# power.net
KiCad netlist of a schematic drawn in Altium Designer
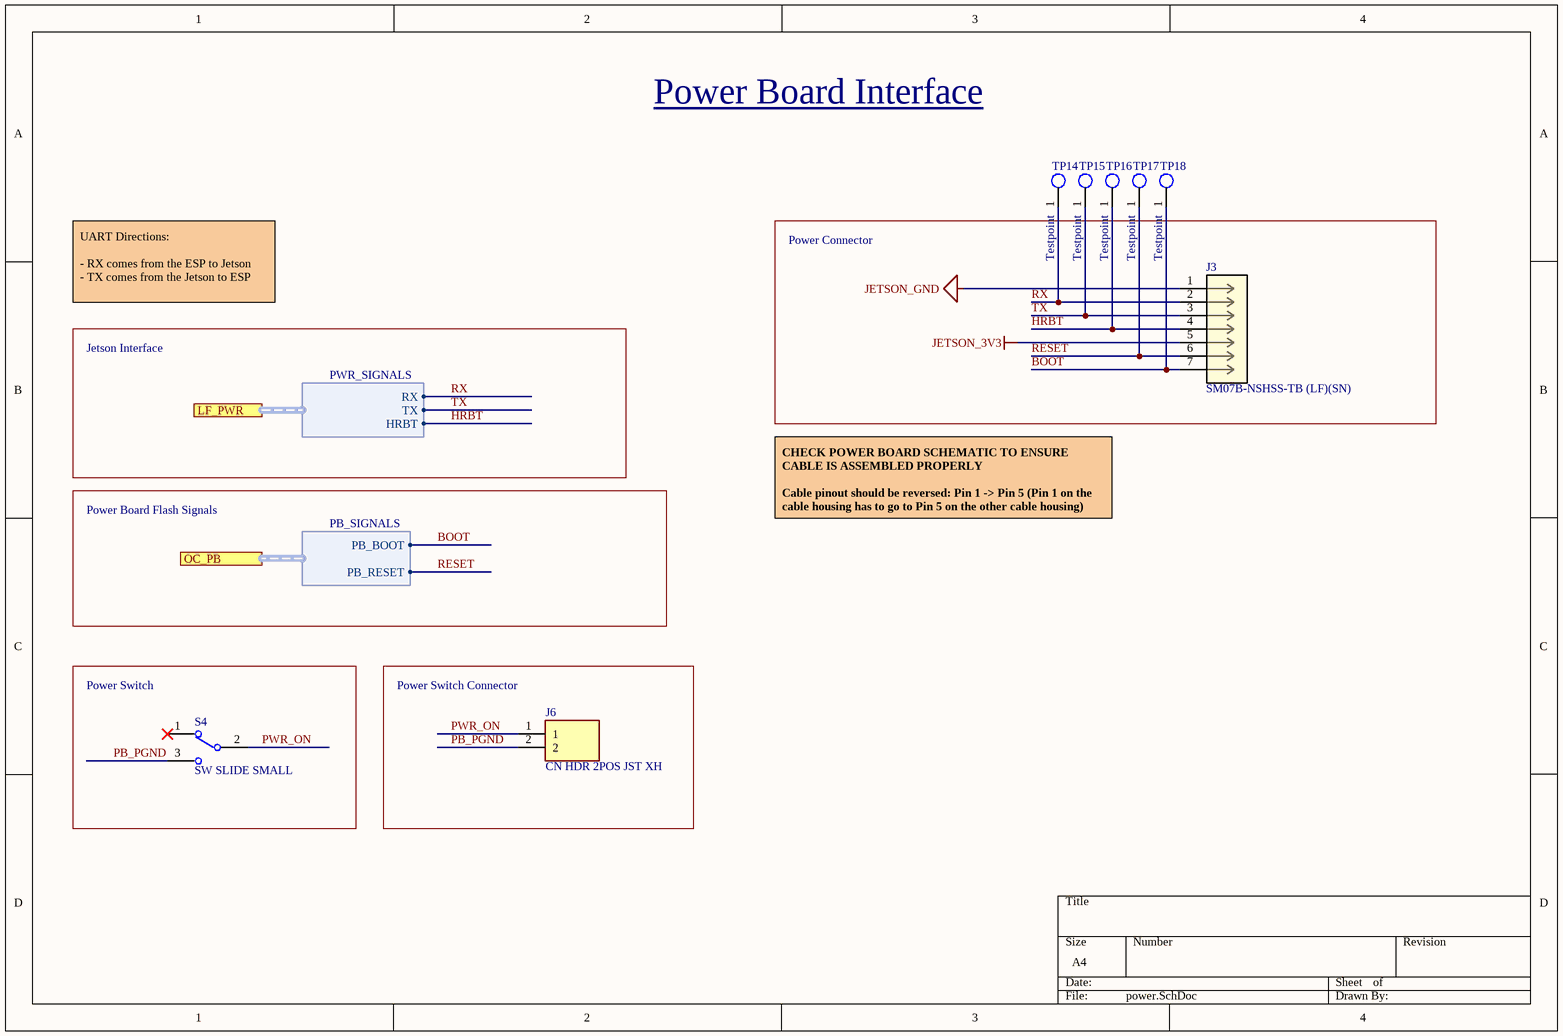
[diagram p0: power.SchDoc]

(export (version "E")
  (design (tool "Eeschema 10.0.6"))
  (components
    (comp (ref "J3")
      (value "SM07B-NSHSS-TB (LF)(SN)")
      (footprint "JST_SM07B-NSHSS-TB_(LF)(SN)")
      (description "Connector Header Surface Mount, Right Angle 7 position 0.039\" (1.00mm)")
      (fields (field (name "MP") "SM12B-NSHSS-TB (LF)(SN)") (field (name "MF") "JST Sales America Inc."))
      (libsource (lib "Connector_Library") (part "CN 7POS JST NSH SMT RA"))
    )
    (comp (ref "J6")
      (value "CN HDR 2POS JST XH")
      (footprint "JST_B2B-XH-A(LF)(SN)")
      (description "Connector Header Through Hole 2 position 0.098 _2.50mm_\r\nJST XH")
      (fields (field (name "MP") "B2B-XH-A_LF__SN_") (field (name "MF") "JST Sales"))
      (libsource (lib "Connector_Library") (part "CN HDR 2POS JST XH"))
    )
    (comp (ref "S4")
      (value "SW SLIDE SMALL")
      (footprint "SW SLIDE SMALL")
      (description "Slide Switch SPDT Surface Mount, Right Angle")
      (fields (field (name "MF") "C&K") (field (name "MP") "JS102011SAQN"))
      (libsource (lib "Switch_Library") (part "SW SLIDE SMALL"))
    )
    (comp (ref "TP14")
      (value "Testpoint")
      (footprint "TP_1mm")
      (fields (field (name "PART NUMBER") "TP_1MM"))
      (libsource (lib "Connector_Library") (part "Testpoint"))
    )
    (comp (ref "TP15")
      (value "Testpoint")
      (footprint "TP_1mm")
      (fields (field (name "PART NUMBER") "TP_1MM"))
      (libsource (lib "Connector_Library") (part "Testpoint"))
    )
    (comp (ref "TP16")
      (value "Testpoint")
      (footprint "TP_1mm")
      (fields (field (name "PART NUMBER") "TP_1MM"))
      (libsource (lib "Connector_Library") (part "Testpoint"))
    )
    (comp (ref "TP17")
      (value "Testpoint")
      (footprint "TP_1mm")
      (fields (field (name "PART NUMBER") "TP_1MM"))
      (libsource (lib "Connector_Library") (part "Testpoint"))
    )
    (comp (ref "TP18")
      (value "Testpoint")
      (footprint "TP_1mm")
      (fields (field (name "PART NUMBER") "TP_1MM"))
      (libsource (lib "Connector_Library") (part "Testpoint"))
    )
  )
  (nets
    (net (code "4") (name "/BOOT") (class "Default")
      (node (ref "J3") (pin "7") (pinfunction "7_7") (pintype "passive"))
      (node (ref "TP18") (pin "1") (pinfunction "TP_1") (pintype "passive"))
    )
    (net (code "5") (name "/HRBT") (class "Default")
      (node (ref "J3") (pin "4") (pinfunction "4_4") (pintype "passive"))
      (node (ref "TP16") (pin "1") (pinfunction "TP_1") (pintype "passive"))
    )
    (net (code "6") (name "/PB_PGND") (class "Default")
      (node (ref "J6") (pin "2") (pinfunction "2_2") (pintype "passive"))
      (node (ref "S4") (pin "3") (pinfunction "3_3") (pintype "passive"))
    )
    (net (code "7") (name "/PWR_ON") (class "Default")
      (node (ref "J6") (pin "1") (pinfunction "1_1") (pintype "passive"))
      (node (ref "S4") (pin "2") (pinfunction "2_2") (pintype "passive"))
    )
    (net (code "8") (name "/RESET") (class "Default")
      (node (ref "J3") (pin "6") (pinfunction "6_6") (pintype "passive"))
      (node (ref "TP17") (pin "1") (pinfunction "TP_1") (pintype "passive"))
    )
    (net (code "9") (name "/RX") (class "Default")
      (node (ref "J3") (pin "2") (pinfunction "2_2") (pintype "passive"))
      (node (ref "TP14") (pin "1") (pinfunction "TP_1") (pintype "passive"))
    )
    (net (code "10") (name "/TX") (class "Default")
      (node (ref "J3") (pin "3") (pinfunction "3_3") (pintype "passive"))
      (node (ref "TP15") (pin "1") (pinfunction "TP_1") (pintype "passive"))
    )
    (net (code "13") (name "JETSON_3V3") (class "Default")
      (node (ref "J3") (pin "5") (pinfunction "5_5") (pintype "passive"))
    )
    (net (code "14") (name "JETSON_GND") (class "Default")
      (node (ref "J3") (pin "1") (pinfunction "1_1") (pintype "passive"))
    )
    (net (code "15") (name "unconnected-(S4-Pad1)") (class "Default")
      (node (ref "S4") (pin "1") (pinfunction "1_1") (pintype "passive+no_connect"))
    )
  )
)
